# ESP32_CAN_V2-power.net
KiCad netlist of a schematic drawn in Altium Designer
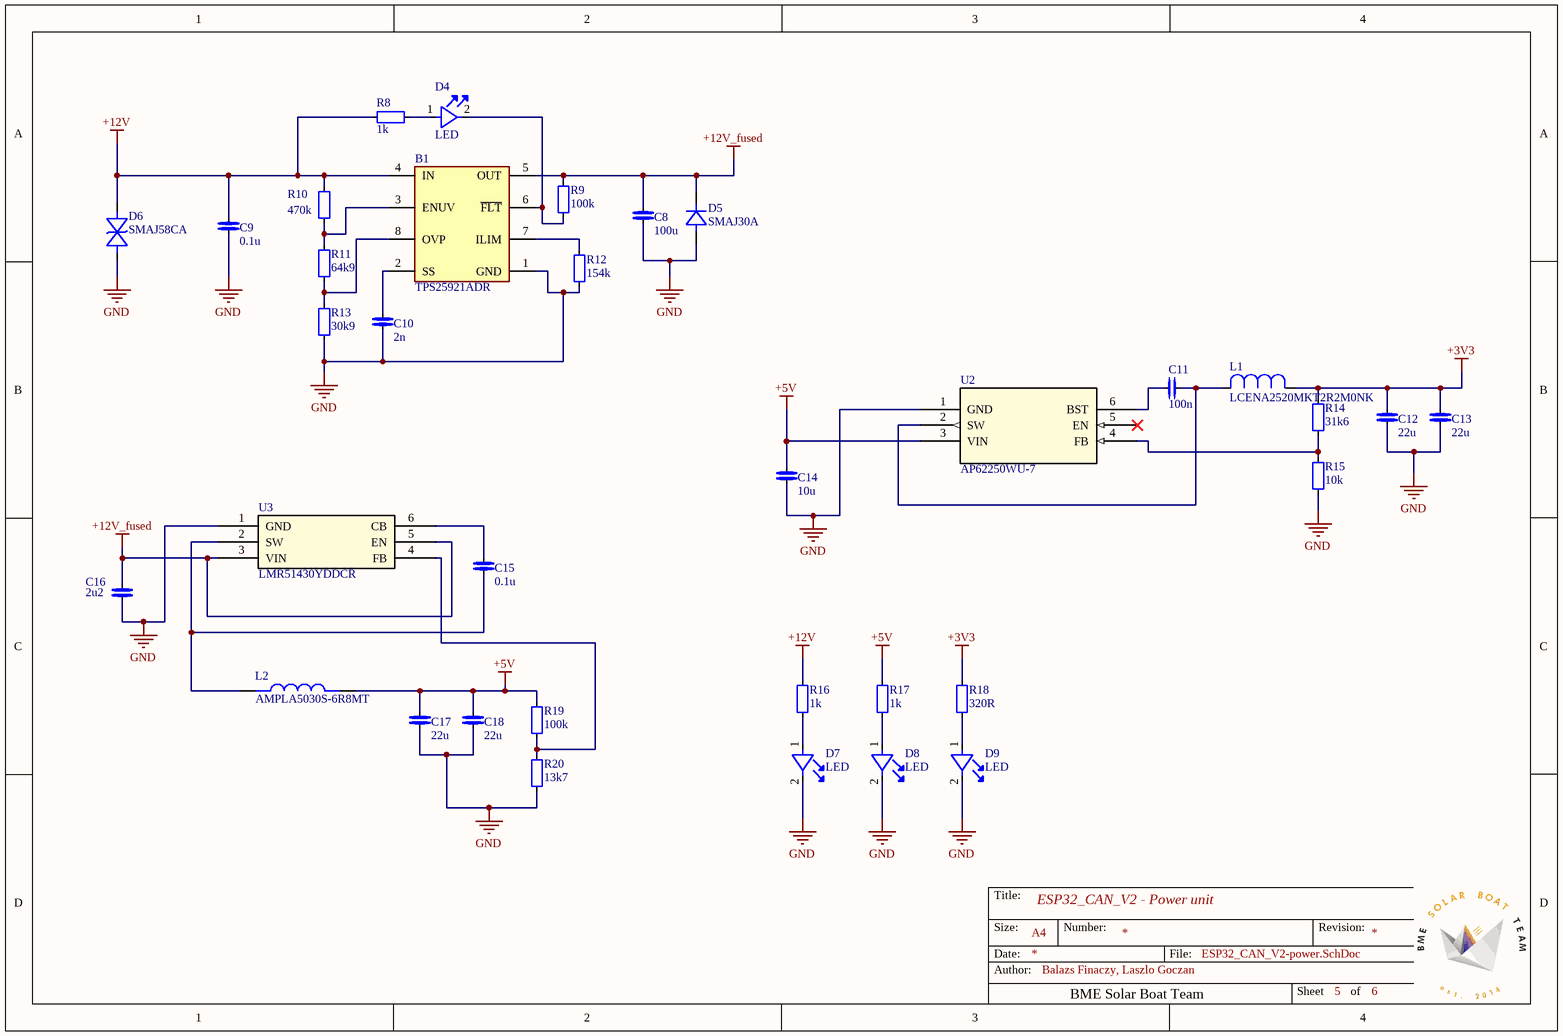
[diagram p0: ESP32_CAN_V2-power.SchDoc]

(export (version "E")
  (design (tool "Eeschema 10.0.6"))
  (components
    (comp (ref "B1")
      (value "TPS25921ADR")
      (footprint "SOIC127P600X175-8N")
      (description "18V, 1.6A, 90m eFuse with Adjustable +/-2% Accurate Current Limit")
      (fields (field (name "MOUSER PART NUMBER") "595-TPS25921ADR"))
      (libsource (lib "ESP32_CAN_V2") (part "TPS25921ADR"))
    )
    (comp (ref "C8") (value "100u") (footprint "C1206") (libsource (lib "ESP32_CAN_V2") (part "C")))
    (comp (ref "C9") (value "0.1u") (footprint "C0603") (libsource (lib "ESP32_CAN_V2") (part "C")))
    (comp (ref "C10") (value "2n") (footprint "C0603") (libsource (lib "ESP32_CAN_V2") (part "C")))
    (comp (ref "C11") (value "100n") (footprint "C0603") (libsource (lib "ESP32_CAN_V2") (part "C")))
    (comp (ref "C12") (value "22u") (footprint "C0805") (libsource (lib "ESP32_CAN_V2") (part "C")))
    (comp (ref "C13") (value "22u") (footprint "C0805") (libsource (lib "ESP32_CAN_V2") (part "C")))
    (comp (ref "C14") (value "10u") (footprint "C0805") (libsource (lib "ESP32_CAN_V2") (part "C")))
    (comp (ref "C15") (value "0.1u") (footprint "C0603") (libsource (lib "ESP32_CAN_V2") (part "C")))
    (comp (ref "C16") (value "2u2") (footprint "C0805") (libsource (lib "ESP32_CAN_V2") (part "C")))
    (comp (ref "C17") (value "22u") (footprint "C0805") (libsource (lib "ESP32_CAN_V2") (part "C")))
    (comp (ref "C18") (value "22u") (footprint "C0805") (libsource (lib "ESP32_CAN_V2") (part "C")))
    (comp (ref "D4")
      (value "LED")
      (footprint "LED")
      (description "150060RS83000")
      (libsource (lib "ESP32_CAN_V2") (part "LED"))
    )
    (comp (ref "D5")
      (value "SMAJ30A")
      (footprint "SMASeries_LTF")
      (description "No Description Available")
      (fields (field (name "COPYRIGHT") "Copyright (C) 2026 Ultra Librarian. All rights reserved."))
      (libsource (lib "ESP32_CAN_V2") (part "SMAJ30A"))
    )
    (comp (ref "D6")
      (value "SMAJ58CA")
      (footprint "SMASeries_LTF")
      (description "No Description Available")
      (fields (field (name "COPYRIGHT") "Copyright (C) 2026 Ultra Librarian. All rights reserved."))
      (libsource (lib "ESP32_CAN_V2") (part "SMAJ58CA"))
    )
    (comp (ref "D7")
      (value "LED")
      (footprint "LED")
      (description "150060AS83000")
      (fields (field (name "MANUFACTURER_PART_NUMBER") "710-150060AS83000"))
      (libsource (lib "ESP32_CAN_V2") (part "LED"))
    )
    (comp (ref "D8")
      (value "LED")
      (footprint "LED")
      (description "150060YS83000")
      (fields (field (name "MANUFACTURER_PART_NUMBER") "710-150060YS83000"))
      (libsource (lib "ESP32_CAN_V2") (part "LED"))
    )
    (comp (ref "D9")
      (value "LED")
      (footprint "LED")
      (description "150060VS83000")
      (fields (field (name "MANUFACTURER_PART_NUMBER") "710-150060VS83000"))
      (libsource (lib "ESP32_CAN_V2") (part "LED"))
    )
    (comp (ref "L1")
      (value "LCENA2520MKT2R2M0NK")
      (footprint "IND_LCEN_2520MK_TAY")
      (description "No Description Available")
      (fields (field (name "COPYRIGHT") "Copyright (C) 2026 Ultra Librarian. All rights reserved."))
      (libsource (lib "ESP32_CAN_V2") (part "L"))
    )
    (comp (ref "L2")
      (value "AMPLA5030S-6R8MT")
      (footprint "IND_AMPLA5030S-6R8MT")
      (fields (field (name "MF") "Abracon LLC"))
      (libsource (lib "ESP32_CAN_V2") (part "AMPLA5030S-6R8MT"))
    )
    (comp (ref "R8") (value "1k") (footprint "R0603") (libsource (lib "ESP32_CAN_V2") (part "R")))
    (comp (ref "R9") (value "100k") (footprint "R0603") (libsource (lib "ESP32_CAN_V2") (part "R")))
    (comp (ref "R10") (value "470k") (footprint "R0603") (libsource (lib "ESP32_CAN_V2") (part "R")))
    (comp (ref "R11") (value "64k9") (footprint "R0603") (libsource (lib "ESP32_CAN_V2") (part "R")))
    (comp (ref "R12") (value "154k") (footprint "R0603") (libsource (lib "ESP32_CAN_V2") (part "R")))
    (comp (ref "R13") (value "30k9") (footprint "R0603") (libsource (lib "ESP32_CAN_V2") (part "R")))
    (comp (ref "R14") (value "31k6") (footprint "R0603") (libsource (lib "ESP32_CAN_V2") (part "R")))
    (comp (ref "R15") (value "10k") (footprint "R0603") (libsource (lib "ESP32_CAN_V2") (part "R")))
    (comp (ref "R16") (value "1k") (footprint "R0603") (libsource (lib "ESP32_CAN_V2") (part "R")))
    (comp (ref "R17") (value "1k") (footprint "R0603") (libsource (lib "ESP32_CAN_V2") (part "R")))
    (comp (ref "R18") (value "320R") (footprint "R0603") (libsource (lib "ESP32_CAN_V2") (part "R")))
    (comp (ref "R19") (value "100k") (footprint "R0603") (libsource (lib "ESP32_CAN_V2") (part "R")))
    (comp (ref "R20") (value "13k7") (footprint "R0603") (libsource (lib "ESP32_CAN_V2") (part "R")))
    (comp (ref "U2")
      (value "AP62250WU-7")
      (footprint "TSOT26STANDARD_DIO")
      (description "No Description Available")
      (fields (field (name "COPYRIGHT") "Copyright (C) 2026 Ultra Librarian. All rights reserved."))
      (libsource (lib "ESP32_CAN_V2") (part "AP62250WU-7"))
    )
    (comp (ref "U3")
      (value "LMR51430YDDCR")
      (footprint "SOT-23-THIN-6_DDC_TEX")
      (fields (field (name "COPYRIGHT") "Copyright (C) 2025 Ultra Librarian. All rights reserved."))
      (libsource (lib "ESP32_CAN_V2") (part "LMR51430YDDCR"))
    )
  )
  (nets
    (net (code "1") (name "+3V3") (class "Default")
      (node (ref "C12") (pin "2") (pinfunction "2_2") (pintype "passive"))
      (node (ref "C13") (pin "2") (pinfunction "2_2") (pintype "passive"))
      (node (ref "L1") (pin "1") (pinfunction "1_1") (pintype "passive"))
      (node (ref "R14") (pin "2") (pinfunction "1_2") (pintype "passive"))
      (node (ref "R18") (pin "2") (pinfunction "1_2") (pintype "passive"))
    )
    (net (code "2") (name "+5V") (class "Default")
      (node (ref "C14") (pin "2") (pinfunction "2_2") (pintype "passive"))
      (node (ref "C17") (pin "2") (pinfunction "2_2") (pintype "passive"))
      (node (ref "C18") (pin "2") (pinfunction "2_2") (pintype "passive"))
      (node (ref "L2") (pin "2") (pinfunction "2_2") (pintype "passive"))
      (node (ref "R17") (pin "2") (pinfunction "1_2") (pintype "passive"))
      (node (ref "R19") (pin "2") (pinfunction "1_2") (pintype "passive"))
      (node (ref "U2") (pin "3") (pinfunction "VIN_3") (pintype "power_in"))
    )
    (net (code "3") (name "+12V") (class "Default")
      (node (ref "B1") (pin "4") (pinfunction "IN_4") (pintype "passive"))
      (node (ref "C9") (pin "2") (pinfunction "2_2") (pintype "passive"))
      (node (ref "D6") (pin "1") (pinfunction "1_1") (pintype "passive"))
      (node (ref "R10") (pin "2") (pinfunction "1_2") (pintype "passive"))
      (node (ref "R16") (pin "2") (pinfunction "1_2") (pintype "passive"))
      (node (ref "R8") (pin "2") (pinfunction "1_2") (pintype "passive"))
    )
    (net (code "4") (name "+12V_fused") (class "Default")
      (node (ref "B1") (pin "5") (pinfunction "OUT_5") (pintype "passive"))
      (node (ref "C16") (pin "2") (pinfunction "2_2") (pintype "passive"))
      (node (ref "C8") (pin "2") (pinfunction "2_2") (pintype "passive"))
      (node (ref "D5") (pin "1") (pinfunction "1_1") (pintype "passive"))
      (node (ref "R9") (pin "2") (pinfunction "1_2") (pintype "passive"))
      (node (ref "U3") (pin "3") (pinfunction "VIN_3") (pintype "power_in"))
      (node (ref "U3") (pin "5") (pinfunction "EN_5") (pintype "passive"))
    )
    (net (code "5") (name "GND") (class "Default")
      (node (ref "B1") (pin "1") (pinfunction "GND_1") (pintype "passive"))
      (node (ref "C10") (pin "1") (pinfunction "1_1") (pintype "passive"))
      (node (ref "C12") (pin "1") (pinfunction "1_1") (pintype "passive"))
      (node (ref "C13") (pin "1") (pinfunction "1_1") (pintype "passive"))
      (node (ref "C14") (pin "1") (pinfunction "1_1") (pintype "passive"))
      (node (ref "C16") (pin "1") (pinfunction "1_1") (pintype "passive"))
      (node (ref "C17") (pin "1") (pinfunction "1_1") (pintype "passive"))
      (node (ref "C18") (pin "1") (pinfunction "1_1") (pintype "passive"))
      (node (ref "C8") (pin "1") (pinfunction "1_1") (pintype "passive"))
      (node (ref "C9") (pin "1") (pinfunction "1_1") (pintype "passive"))
      (node (ref "D5") (pin "2") (pinfunction "2_2") (pintype "passive"))
      (node (ref "D6") (pin "2") (pinfunction "2_2") (pintype "passive"))
      (node (ref "D7") (pin "2") (pinfunction "2_2") (pintype "passive"))
      (node (ref "D8") (pin "2") (pinfunction "2_2") (pintype "passive"))
      (node (ref "D9") (pin "2") (pinfunction "2_2") (pintype "passive"))
      (node (ref "R12") (pin "1") (pinfunction "0_1") (pintype "passive"))
      (node (ref "R13") (pin "1") (pinfunction "0_1") (pintype "passive"))
      (node (ref "R15") (pin "1") (pinfunction "0_1") (pintype "passive"))
      (node (ref "R20") (pin "1") (pinfunction "0_1") (pintype "passive"))
      (node (ref "U2") (pin "1") (pinfunction "GND_1") (pintype "power_in"))
      (node (ref "U3") (pin "1") (pinfunction "GND_1") (pintype "power_in"))
    )
    (net (code "6") (name "Net-(B1-ENUV)") (class "Default")
      (node (ref "B1") (pin "3") (pinfunction "ENUV_3") (pintype "passive"))
      (node (ref "R10") (pin "1") (pinfunction "0_1") (pintype "passive"))
      (node (ref "R11") (pin "2") (pinfunction "1_2") (pintype "passive"))
    )
    (net (code "7") (name "Net-(B1-ILIM)") (class "Default")
      (node (ref "B1") (pin "7") (pinfunction "ILIM_7") (pintype "passive"))
      (node (ref "R12") (pin "2") (pinfunction "1_2") (pintype "passive"))
    )
    (net (code "8") (name "Net-(B1-OVP)") (class "Default")
      (node (ref "B1") (pin "8") (pinfunction "OVP_8") (pintype "passive"))
      (node (ref "R11") (pin "1") (pinfunction "0_1") (pintype "passive"))
      (node (ref "R13") (pin "2") (pinfunction "1_2") (pintype "passive"))
    )
    (net (code "9") (name "Net-(B1-SS)") (class "Default")
      (node (ref "B1") (pin "2") (pinfunction "SS_2") (pintype "passive"))
      (node (ref "C10") (pin "2") (pinfunction "2_2") (pintype "passive"))
    )
    (net (code "10") (name "Net-(B1-~{FLT})") (class "Default")
      (node (ref "B1") (pin "6") (pinfunction "~{FLT}_6") (pintype "passive"))
      (node (ref "D4") (pin "2") (pinfunction "2_2") (pintype "passive"))
      (node (ref "R9") (pin "1") (pinfunction "0_1") (pintype "passive"))
    )
    (net (code "11") (name "Net-(R8-0)") (class "Default")
      (node (ref "D4") (pin "1") (pinfunction "1_1") (pintype "passive"))
      (node (ref "R8") (pin "1") (pinfunction "0_1") (pintype "passive"))
    )
    (net (code "12") (name "Net-(R14-0)") (class "Default")
      (node (ref "R14") (pin "1") (pinfunction "0_1") (pintype "passive"))
      (node (ref "R15") (pin "2") (pinfunction "1_2") (pintype "passive"))
      (node (ref "U2") (pin "4") (pinfunction "FB_4") (pintype "input"))
    )
    (net (code "13") (name "Net-(R16-0)") (class "Default")
      (node (ref "D7") (pin "1") (pinfunction "1_1") (pintype "passive"))
      (node (ref "R16") (pin "1") (pinfunction "0_1") (pintype "passive"))
    )
    (net (code "14") (name "Net-(R17-0)") (class "Default")
      (node (ref "D8") (pin "1") (pinfunction "1_1") (pintype "passive"))
      (node (ref "R17") (pin "1") (pinfunction "0_1") (pintype "passive"))
    )
    (net (code "15") (name "Net-(R18-0)") (class "Default")
      (node (ref "D9") (pin "1") (pinfunction "1_1") (pintype "passive"))
      (node (ref "R18") (pin "1") (pinfunction "0_1") (pintype "passive"))
    )
    (net (code "16") (name "Net-(R19-0)") (class "Default")
      (node (ref "R19") (pin "1") (pinfunction "0_1") (pintype "passive"))
      (node (ref "R20") (pin "2") (pinfunction "1_2") (pintype "passive"))
      (node (ref "U3") (pin "4") (pinfunction "FB_4") (pintype "passive"))
    )
    (net (code "17") (name "Net-(U2-BST)") (class "Default")
      (node (ref "C11") (pin "1") (pinfunction "1_1") (pintype "passive"))
      (node (ref "U2") (pin "6") (pinfunction "BST_6") (pintype "power_in"))
    )
    (net (code "18") (name "Net-(U2-SW)") (class "Default")
      (node (ref "C11") (pin "2") (pinfunction "2_2") (pintype "passive"))
      (node (ref "L1") (pin "2") (pinfunction "2_2") (pintype "passive"))
      (node (ref "U2") (pin "2") (pinfunction "SW_2") (pintype "output"))
    )
    (net (code "19") (name "Net-(U3-CB)") (class "Default")
      (node (ref "C15") (pin "2") (pinfunction "2_2") (pintype "passive"))
      (node (ref "U3") (pin "6") (pinfunction "CB_6") (pintype "power_in"))
    )
    (net (code "20") (name "Net-(U3-SW)") (class "Default")
      (node (ref "C15") (pin "1") (pinfunction "1_1") (pintype "passive"))
      (node (ref "L2") (pin "1") (pinfunction "1_1") (pintype "passive"))
      (node (ref "U3") (pin "2") (pinfunction "SW_2") (pintype "power_in"))
    )
    (net (code "21") (name "unconnected-(U2-EN-Pad5)") (class "Default")
      (node (ref "U2") (pin "5") (pinfunction "EN_5") (pintype "input+no_connect"))
    )
  )
)
